# feather_adapter.net
KiCad netlist of a schematic drawn in EAGLE
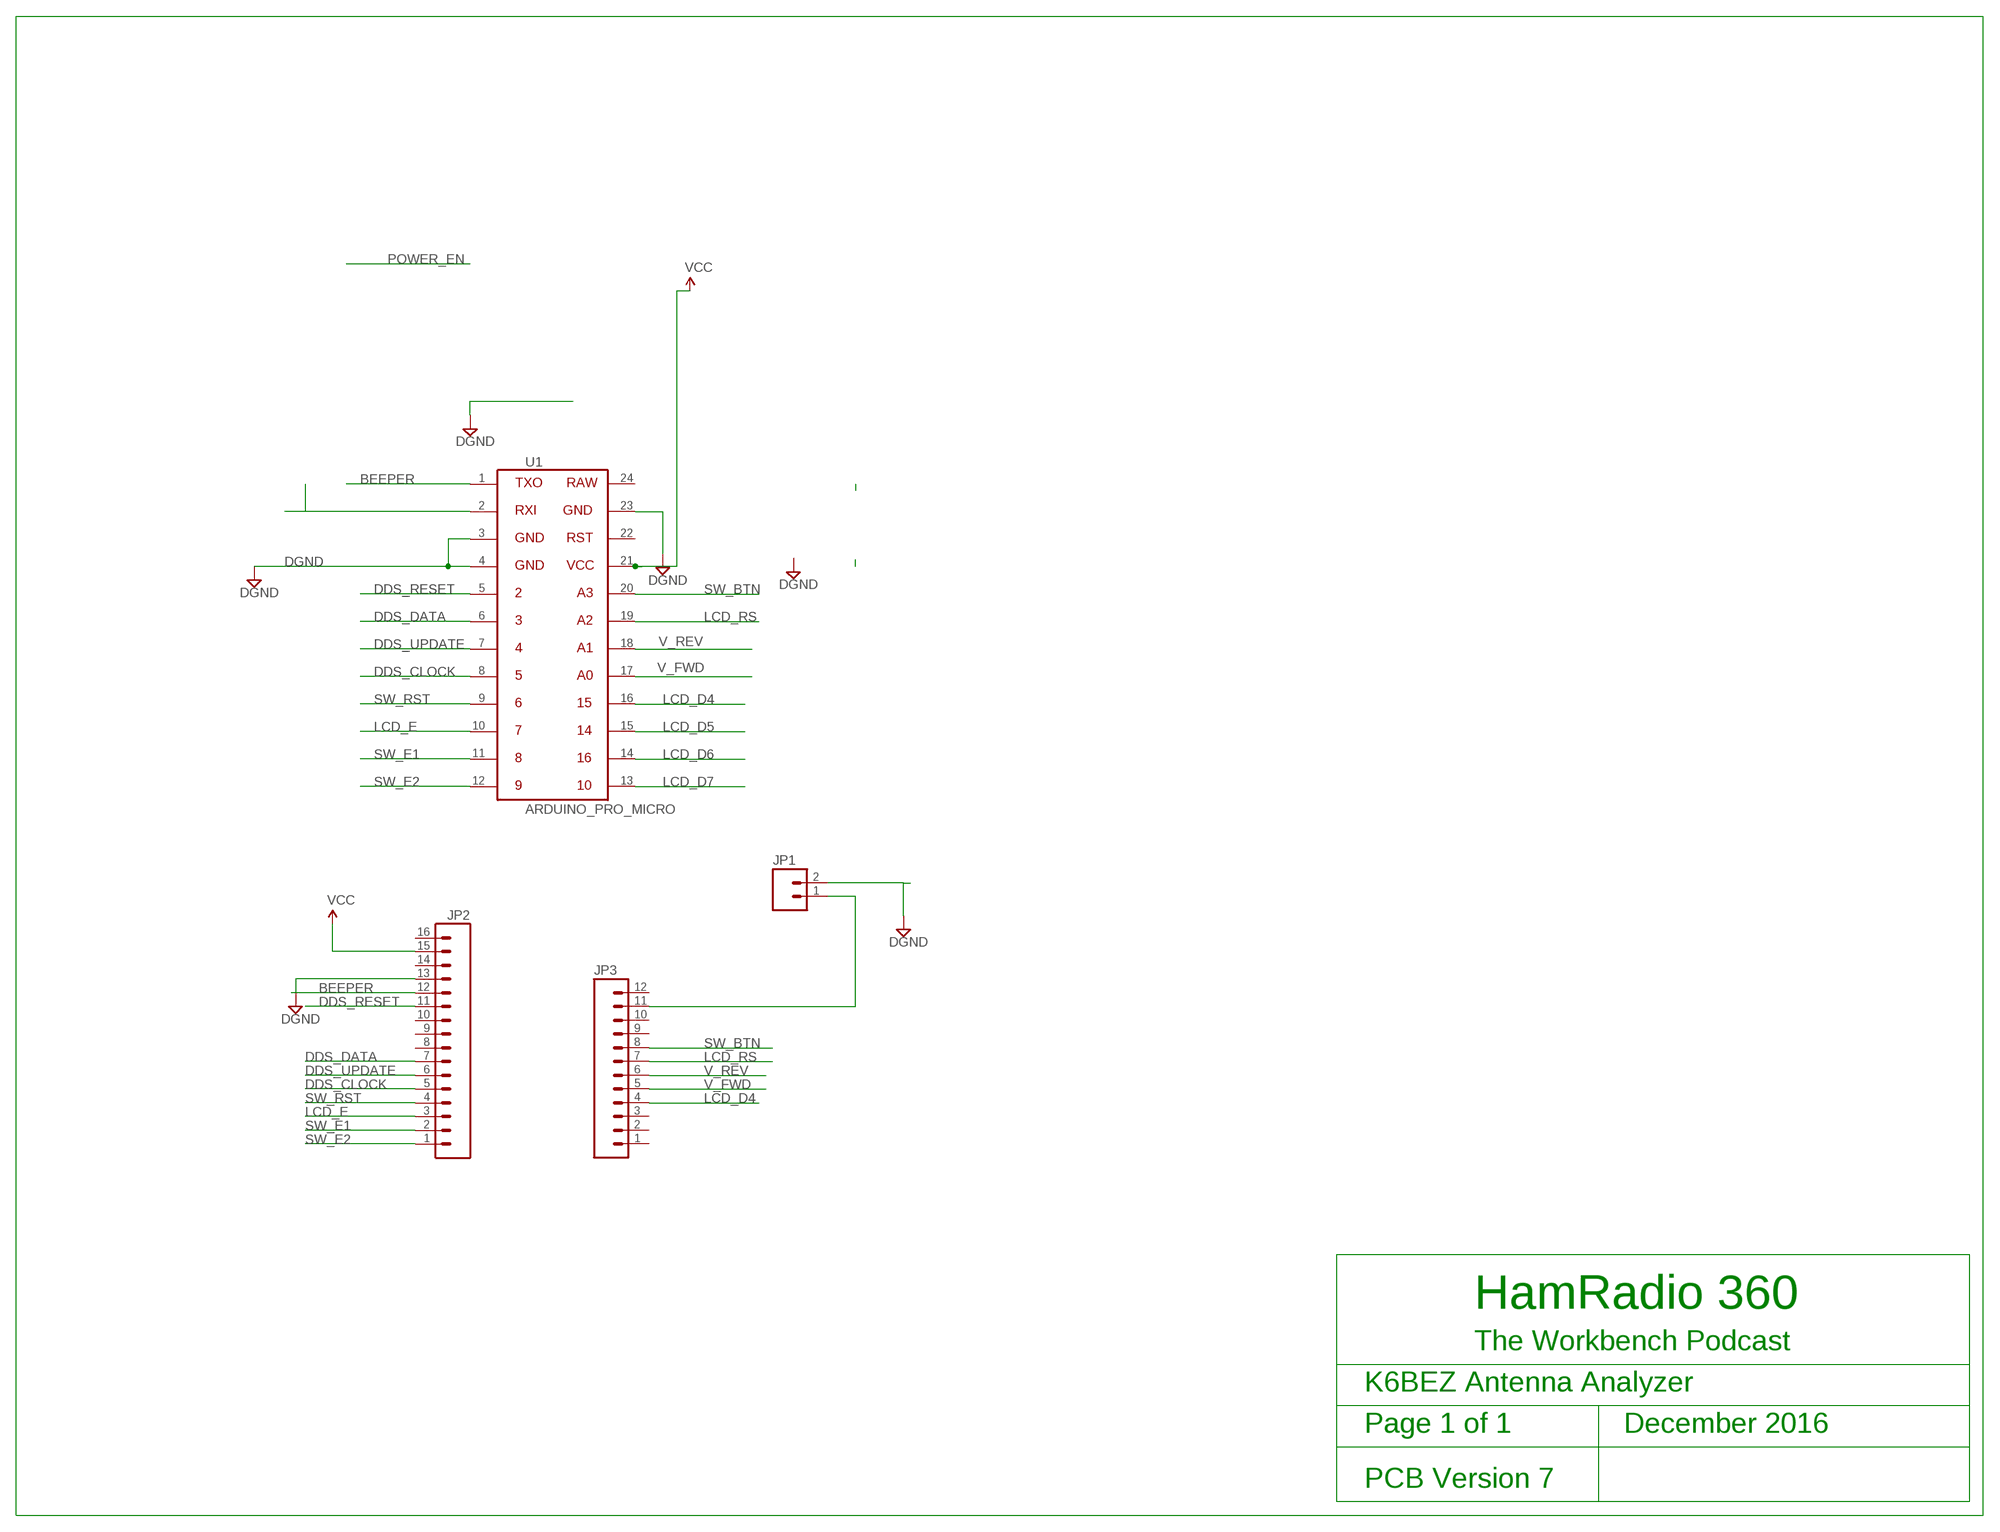
[diagram p0: schematic, sheet 1]

(export (version "E")
  (design (tool "Eeschema 10.0.6"))
  (components
    (comp (ref "JP1")
      (value "M02PTH")
      (footprint "eagle-import:1X02")
      (libsource (lib "eagle-import") (part "M02PTH"))
    )
    (comp (ref "JP2")
      (value "M16PTH")
      (footprint "eagle-import:1X16")
      (libsource (lib "eagle-import") (part "M16PTH"))
    )
    (comp (ref "JP3")
      (value "M12PTH")
      (footprint "eagle-import:1X12")
      (libsource (lib "eagle-import") (part "M12PTH"))
    )
    (comp (ref "U1")
      (value "ARDUINO_PRO_MICRO")
      (footprint "eagle-import:ARDUINO_PRO_MICRO")
      (libsource (lib "eagle-import") (part "ARDUINO_PRO_MICRO"))
    )
  )
  (nets
    (net (code "1") (name "/BEEPER") (class "Default")
      (node (ref "JP2") (pin "12") (pinfunction "12_12") (pintype "passive"))
      (node (ref "U1") (pin "1") (pinfunction "1_1") (pintype "input"))
    )
    (net (code "2") (name "/DDS_CLOCK") (class "Default")
      (node (ref "JP2") (pin "5") (pinfunction "5_5") (pintype "passive"))
      (node (ref "U1") (pin "8") (pinfunction "8_8") (pintype "input"))
    )
    (net (code "3") (name "/DDS_DATA") (class "Default")
      (node (ref "JP2") (pin "7") (pinfunction "7_7") (pintype "passive"))
      (node (ref "U1") (pin "6") (pinfunction "6_6") (pintype "input"))
    )
    (net (code "4") (name "/DDS_RESET") (class "Default")
      (node (ref "JP2") (pin "11") (pinfunction "11_11") (pintype "passive"))
      (node (ref "U1") (pin "5") (pinfunction "5_5") (pintype "input"))
    )
    (net (code "5") (name "/DDS_UPDATE") (class "Default")
      (node (ref "JP2") (pin "6") (pinfunction "6_6") (pintype "passive"))
      (node (ref "U1") (pin "7") (pinfunction "7_7") (pintype "input"))
    )
    (net (code "6") (name "/LCD_D4") (class "Default")
      (node (ref "JP3") (pin "4") (pinfunction "4_4") (pintype "passive"))
      (node (ref "U1") (pin "16") (pinfunction "16_16") (pintype "input"))
    )
    (net (code "7") (name "/LCD_D5") (class "Default")
      (node (ref "U1") (pin "15") (pinfunction "15_15") (pintype "tri_state"))
    )
    (net (code "8") (name "/LCD_D6") (class "Default")
      (node (ref "U1") (pin "14") (pinfunction "14_14") (pintype "input"))
    )
    (net (code "9") (name "/LCD_D7") (class "Default")
      (node (ref "U1") (pin "13") (pinfunction "13_13") (pintype "input"))
    )
    (net (code "10") (name "/LCD_E") (class "Default")
      (node (ref "JP2") (pin "3") (pinfunction "3_3") (pintype "passive"))
      (node (ref "U1") (pin "10") (pinfunction "10_10") (pintype "input"))
    )
    (net (code "11") (name "/LCD_RS") (class "Default")
      (node (ref "JP3") (pin "7") (pinfunction "7_7") (pintype "passive"))
      (node (ref "U1") (pin "19") (pinfunction "19_19") (pintype "input"))
    )
    (net (code "14") (name "/SW_BTN") (class "Default")
      (node (ref "JP3") (pin "8") (pinfunction "8_8") (pintype "passive"))
      (node (ref "U1") (pin "20") (pinfunction "20_20") (pintype "input"))
    )
    (net (code "15") (name "/SW_E1") (class "Default")
      (node (ref "JP2") (pin "2") (pinfunction "2_2") (pintype "passive"))
      (node (ref "U1") (pin "11") (pinfunction "11_11") (pintype "input"))
    )
    (net (code "16") (name "/SW_E2") (class "Default")
      (node (ref "JP2") (pin "1") (pinfunction "1_1") (pintype "passive"))
      (node (ref "U1") (pin "12") (pinfunction "12_12") (pintype "input"))
    )
    (net (code "17") (name "/SW_RST") (class "Default")
      (node (ref "JP2") (pin "4") (pinfunction "4_4") (pintype "passive"))
      (node (ref "U1") (pin "9") (pinfunction "9_9") (pintype "input"))
    )
    (net (code "18") (name "/V_FWD") (class "Default")
      (node (ref "JP3") (pin "5") (pinfunction "5_5") (pintype "passive"))
      (node (ref "U1") (pin "17") (pinfunction "17_17") (pintype "input"))
    )
    (net (code "19") (name "/V_REV") (class "Default")
      (node (ref "JP3") (pin "6") (pinfunction "6_6") (pintype "passive"))
      (node (ref "U1") (pin "18") (pinfunction "18_18") (pintype "input"))
    )
    (net (code "20") (name "DGND") (class "Default")
      (node (ref "JP1") (pin "2") (pinfunction "2_2") (pintype "passive"))
      (node (ref "JP2") (pin "13") (pinfunction "13_13") (pintype "passive"))
      (node (ref "U1") (pin "23") (pinfunction "23_23") (pintype "input"))
      (node (ref "U1") (pin "3") (pinfunction "3_3") (pintype "input"))
      (node (ref "U1") (pin "4") (pinfunction "4_4") (pintype "input"))
    )
    (net (code "21") (name "Net-(JP1-Pad1)") (class "Default")
      (node (ref "JP1") (pin "1") (pinfunction "1_1") (pintype "passive"))
      (node (ref "JP3") (pin "11") (pinfunction "11_11") (pintype "passive"))
    )
    (net (code "22") (name "VCC") (class "Default")
      (node (ref "JP2") (pin "15") (pinfunction "15_15") (pintype "passive"))
      (node (ref "U1") (pin "21") (pinfunction "21_21") (pintype "input"))
    )
    (net (code "23") (name "unconnected-(JP2-Pad8)") (class "Default")
      (node (ref "JP2") (pin "8") (pinfunction "8_8") (pintype "passive"))
    )
    (net (code "24") (name "unconnected-(JP2-Pad9)") (class "Default")
      (node (ref "JP2") (pin "9") (pinfunction "9_9") (pintype "passive"))
    )
    (net (code "25") (name "unconnected-(JP2-Pad10)") (class "Default")
      (node (ref "JP2") (pin "10") (pinfunction "10_10") (pintype "passive"))
    )
    (net (code "26") (name "unconnected-(JP2-Pad14)") (class "Default")
      (node (ref "JP2") (pin "14") (pinfunction "14_14") (pintype "passive"))
    )
    (net (code "27") (name "unconnected-(JP2-Pad16)") (class "Default")
      (node (ref "JP2") (pin "16") (pinfunction "16_16") (pintype "passive"))
    )
    (net (code "28") (name "unconnected-(JP3-Pad1)") (class "Default")
      (node (ref "JP3") (pin "1") (pinfunction "1_1") (pintype "passive"))
    )
    (net (code "29") (name "unconnected-(JP3-Pad2)") (class "Default")
      (node (ref "JP3") (pin "2") (pinfunction "2_2") (pintype "passive"))
    )
    (net (code "30") (name "unconnected-(JP3-Pad3)") (class "Default")
      (node (ref "JP3") (pin "3") (pinfunction "3_3") (pintype "passive"))
    )
    (net (code "31") (name "unconnected-(JP3-Pad9)") (class "Default")
      (node (ref "JP3") (pin "9") (pinfunction "9_9") (pintype "passive"))
    )
    (net (code "32") (name "unconnected-(JP3-Pad10)") (class "Default")
      (node (ref "JP3") (pin "10") (pinfunction "10_10") (pintype "passive"))
    )
    (net (code "33") (name "unconnected-(JP3-Pad12)") (class "Default")
      (node (ref "JP3") (pin "12") (pinfunction "12_12") (pintype "passive"))
    )
    (net (code "34") (name "unconnected-(U1-Pad2)") (class "Default")
      (node (ref "U1") (pin "2") (pinfunction "2_2") (pintype "input"))
    )
    (net (code "35") (name "unconnected-(U1-Pad22)") (class "Default")
      (node (ref "U1") (pin "22") (pinfunction "22_22") (pintype "input"))
    )
    (net (code "36") (name "unconnected-(U1-Pad24)") (class "Default")
      (node (ref "U1") (pin "24") (pinfunction "24_24") (pintype "input"))
    )
  )
)
